# EBook.net
KiCad netlist of a schematic drawn in EAGLE
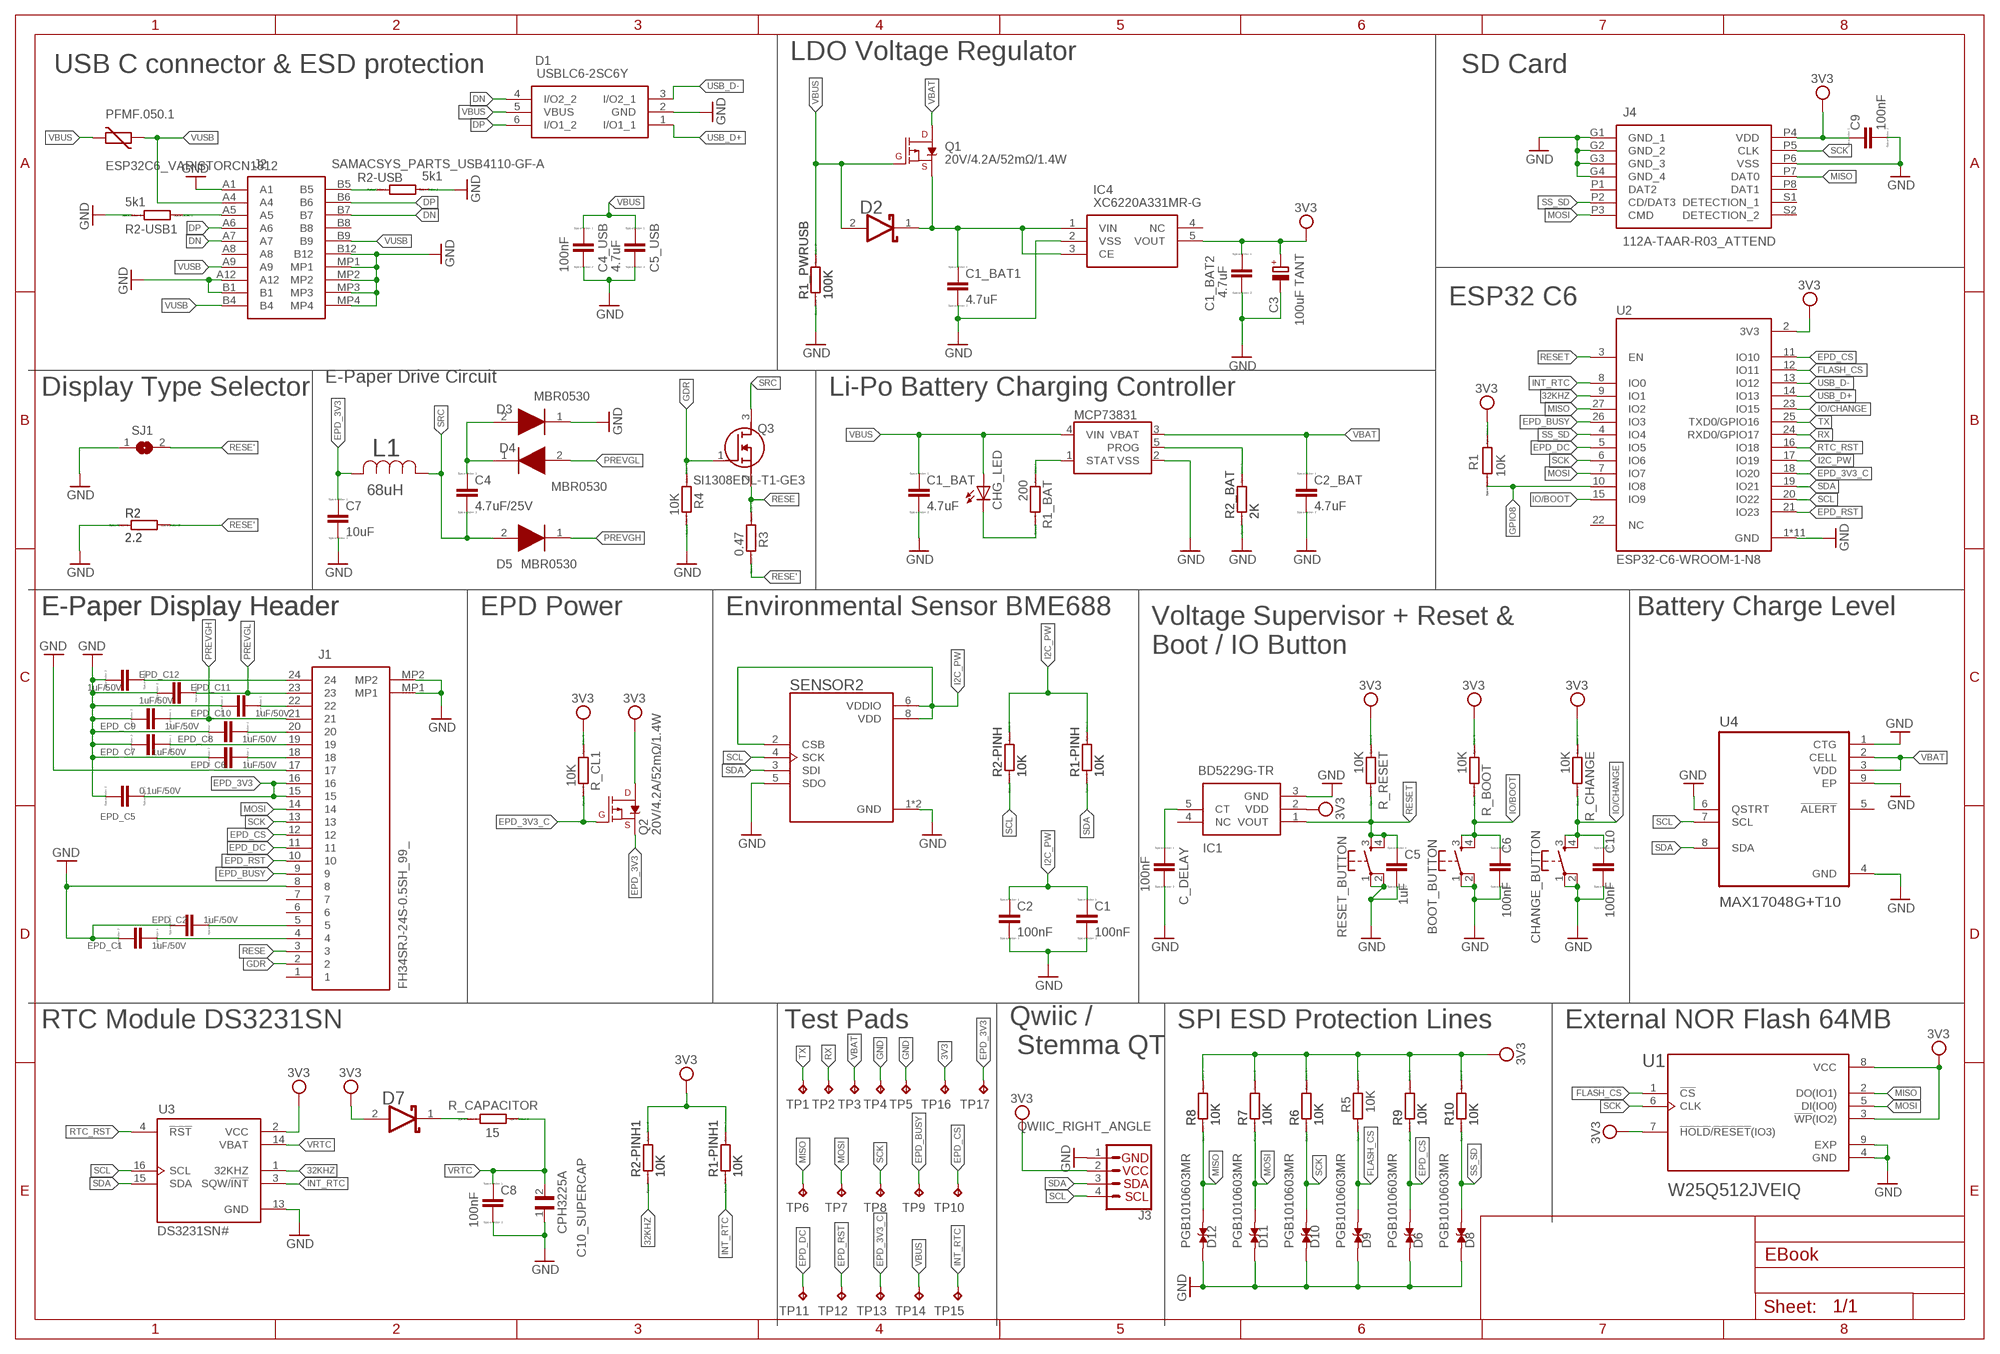
[diagram p0: schematic, sheet 1]

(export (version "E")
  (design (tool "Eeschema 10.0.6"))
  (components
    (comp (ref "BOOT_BUTTON")
      (value "BUTTON_CUSYOMV1")
      (footprint "eagle-import:MYBUTTON")
      (libsource (lib "eagle-import") (part "BUTTON_CUSYOMV1"))
    )
    (comp (ref "C1")
      (value "100nF")
      (footprint "eagle-import:EAGLE-LTSPICE_C0402")
      (libsource (lib "eagle-import") (part "EAGLE-LTSPICE_CC0402"))
    )
    (comp (ref "C1_BAT")
      (value "4.7uF")
      (footprint "eagle-import:EAGLE-LTSPICE_C0402")
      (libsource (lib "eagle-import") (part "EAGLE-LTSPICE_CC0402"))
    )
    (comp (ref "C1_BAT1")
      (value "4.7uF")
      (footprint "eagle-import:EAGLE-LTSPICE_C0402")
      (libsource (lib "eagle-import") (part "EAGLE-LTSPICE_CC0402"))
    )
    (comp (ref "C1_BAT2")
      (value "4.7uF")
      (footprint "eagle-import:EAGLE-LTSPICE_C0402")
      (libsource (lib "eagle-import") (part "EAGLE-LTSPICE_CC0402"))
    )
    (comp (ref "C2")
      (value "100nF")
      (footprint "eagle-import:EAGLE-LTSPICE_C0402")
      (libsource (lib "eagle-import") (part "EAGLE-LTSPICE_CC0402"))
    )
    (comp (ref "C2_BAT")
      (value "4.7uF")
      (footprint "eagle-import:EAGLE-LTSPICE_C0402")
      (libsource (lib "eagle-import") (part "EAGLE-LTSPICE_CC0402"))
    )
    (comp (ref "C3")
      (value "100uF TANT")
      (footprint "eagle-import:RCL_CT3528")
      (libsource (lib "eagle-import") (part "RCL_CPOL-EUCT3528"))
    )
    (comp (ref "C4")
      (value "4.7uF/25V")
      (footprint "eagle-import:EAGLE-LTSPICE_C0402")
      (libsource (lib "eagle-import") (part "EAGLE-LTSPICE_CC0402"))
    )
    (comp (ref "C4_USB")
      (value "100nF")
      (footprint "eagle-import:EAGLE-LTSPICE_C0402")
      (libsource (lib "eagle-import") (part "EAGLE-LTSPICE_CC0402"))
    )
    (comp (ref "C5")
      (value "1uF")
      (footprint "eagle-import:EAGLE-LTSPICE_C0402")
      (libsource (lib "eagle-import") (part "EAGLE-LTSPICE_CC0402"))
    )
    (comp (ref "C5_USB")
      (value "4.7uF")
      (footprint "eagle-import:EAGLE-LTSPICE_C0402")
      (libsource (lib "eagle-import") (part "EAGLE-LTSPICE_CC0402"))
    )
    (comp (ref "C6")
      (value "100nF")
      (footprint "eagle-import:EAGLE-LTSPICE_C0402")
      (libsource (lib "eagle-import") (part "EAGLE-LTSPICE_CC0402"))
    )
    (comp (ref "C7")
      (value "10uF")
      (footprint "eagle-import:EAGLE-LTSPICE_C0402")
      (libsource (lib "eagle-import") (part "EAGLE-LTSPICE_CC0402"))
    )
    (comp (ref "C8")
      (value "100nF")
      (footprint "eagle-import:EAGLE-LTSPICE_C0402")
      (libsource (lib "eagle-import") (part "EAGLE-LTSPICE_CC0402"))
    )
    (comp (ref "C9")
      (value "100nF")
      (footprint "eagle-import:EAGLE-LTSPICE_C0402")
      (libsource (lib "eagle-import") (part "EAGLE-LTSPICE_CC0402"))
    )
    (comp (ref "C10")
      (value "100nF")
      (footprint "eagle-import:EAGLE-LTSPICE_C0402")
      (libsource (lib "eagle-import") (part "EAGLE-LTSPICE_CC0402"))
    )
    (comp (ref "C10_SUPERCAP")
      (value "CPH3225A")
      (footprint "eagle-import:CAPCP3225X100N")
      (fields (field (name "MF") "Seiko Instruments"))
      (libsource (lib "eagle-import") (part "CPH3225A"))
    )
    (comp (ref "CHANGE_BUTTON")
      (value "BUTTON_CUSYOMV1")
      (footprint "eagle-import:MYBUTTON")
      (libsource (lib "eagle-import") (part "BUTTON_CUSYOMV1"))
    )
    (comp (ref "CHG_LED")
      (value "ADAFRUIT_LEDCHIP-LED0603")
      (footprint "eagle-import:ADAFRUIT_CHIP-LED0603")
      (libsource (lib "eagle-import") (part "ADAFRUIT_LEDCHIP-LED0603"))
    )
    (comp (ref "C_DELAY")
      (value "100nF")
      (footprint "eagle-import:EAGLE-LTSPICE_C0402")
      (libsource (lib "eagle-import") (part "EAGLE-LTSPICE_CC0402"))
    )
    (comp (ref "D1")
      (value "USBLC6-2SC6Y")
      (footprint "eagle-import:SOT95P280X145-6N")
      (fields (field (name "MF") "STMicroelectronics"))
      (libsource (lib "eagle-import") (part "USBLC6-2SC6Y"))
    )
    (comp (ref "D2")
      (value "ESP32_WROVER_AVX---SD0805S020S1R0_AVX_SD0805S020S1R0_0_0AVX_SD0805S020S1R0_0_0")
      (footprint "eagle-import:ESP32_WROVER_AVX---SD0805S020S1R0_AVX_SD0805S020S1R0_0")
      (fields
        (field (name "DIGIKEY_PART_NUMBER") "478-7800-1-ND")
        (field (name "MF") "AVX")
        (field (name "MOUSER_PART_NUMBER") "581-SD0805S020S1R0")
      )
      (libsource (lib "eagle-import") (part "ESP32_WROVER_AVX---SD0805S020S1R0_AVX_SD0805S020S1R0_0_0AVX_SD0805S020S1R0_0_0"))
    )
    (comp (ref "D3")
      (value "MBR0530")
      (footprint "eagle-import:SOD3716X135N")
      (fields (field (name "MF") "ON Semiconductor"))
      (libsource (lib "eagle-import") (part "MBR0530"))
    )
    (comp (ref "D4")
      (value "MBR0530")
      (footprint "eagle-import:SOD3716X135N")
      (fields (field (name "MF") "ON Semiconductor"))
      (libsource (lib "eagle-import") (part "MBR0530"))
    )
    (comp (ref "D5")
      (value "MBR0530")
      (footprint "eagle-import:SOD3716X135N")
      (fields (field (name "MF") "ON Semiconductor"))
      (libsource (lib "eagle-import") (part "MBR0530"))
    )
    (comp (ref "D6")
      (value "PGB1010603MR")
      (footprint "eagle-import:DIOC1608X36N")
      (fields (field (name "MF") "Littelfuse Inc."))
      (libsource (lib "eagle-import") (part "PGB1010603MR"))
    )
    (comp (ref "D7")
      (value "ESP32_WROVER_AVX---SD0805S020S1R0_AVX_SD0805S020S1R0_0_0AVX_SD0805S020S1R0_0_0")
      (footprint "eagle-import:ESP32_WROVER_AVX---SD0805S020S1R0_AVX_SD0805S020S1R0_0")
      (fields
        (field (name "DIGIKEY_PART_NUMBER") "478-7800-1-ND")
        (field (name "MF") "AVX")
        (field (name "MOUSER_PART_NUMBER") "581-SD0805S020S1R0")
      )
      (libsource (lib "eagle-import") (part "ESP32_WROVER_AVX---SD0805S020S1R0_AVX_SD0805S020S1R0_0_0AVX_SD0805S020S1R0_0_0"))
    )
    (comp (ref "D8")
      (value "PGB1010603MR")
      (footprint "eagle-import:DIOC1608X36N")
      (fields (field (name "MF") "Littelfuse Inc."))
      (libsource (lib "eagle-import") (part "PGB1010603MR"))
    )
    (comp (ref "D9")
      (value "PGB1010603MR")
      (footprint "eagle-import:DIOC1608X36N")
      (fields (field (name "MF") "Littelfuse Inc."))
      (libsource (lib "eagle-import") (part "PGB1010603MR"))
    )
    (comp (ref "D10")
      (value "PGB1010603MR")
      (footprint "eagle-import:DIOC1608X36N")
      (fields (field (name "MF") "Littelfuse Inc."))
      (libsource (lib "eagle-import") (part "PGB1010603MR"))
    )
    (comp (ref "D11")
      (value "PGB1010603MR")
      (footprint "eagle-import:DIOC1608X36N")
      (fields (field (name "MF") "Littelfuse Inc."))
      (libsource (lib "eagle-import") (part "PGB1010603MR"))
    )
    (comp (ref "D12")
      (value "PGB1010603MR")
      (footprint "eagle-import:DIOC1608X36N")
      (fields (field (name "MF") "Littelfuse Inc."))
      (libsource (lib "eagle-import") (part "PGB1010603MR"))
    )
    (comp (ref "EPD_C1")
      (value "1uF/50V")
      (footprint "eagle-import:EAGLE-LTSPICE_C0402")
      (libsource (lib "eagle-import") (part "EAGLE-LTSPICE_CC0402"))
    )
    (comp (ref "EPD_C2")
      (value "1uF/50V")
      (footprint "eagle-import:EAGLE-LTSPICE_C0402")
      (libsource (lib "eagle-import") (part "EAGLE-LTSPICE_CC0402"))
    )
    (comp (ref "EPD_C5")
      (value "0.1uF/50V")
      (footprint "eagle-import:EAGLE-LTSPICE_C0402")
      (libsource (lib "eagle-import") (part "EAGLE-LTSPICE_CC0402"))
    )
    (comp (ref "EPD_C6")
      (value "1uF/50V")
      (footprint "eagle-import:EAGLE-LTSPICE_C0402")
      (libsource (lib "eagle-import") (part "EAGLE-LTSPICE_CC0402"))
    )
    (comp (ref "EPD_C7")
      (value "1uF/50V")
      (footprint "eagle-import:EAGLE-LTSPICE_C0402")
      (libsource (lib "eagle-import") (part "EAGLE-LTSPICE_CC0402"))
    )
    (comp (ref "EPD_C8")
      (value "1uF/50V")
      (footprint "eagle-import:EAGLE-LTSPICE_C0402")
      (libsource (lib "eagle-import") (part "EAGLE-LTSPICE_CC0402"))
    )
    (comp (ref "EPD_C9")
      (value "1uF/50V")
      (footprint "eagle-import:EAGLE-LTSPICE_C0402")
      (libsource (lib "eagle-import") (part "EAGLE-LTSPICE_CC0402"))
    )
    (comp (ref "EPD_C10")
      (value "1uF/50V")
      (footprint "eagle-import:EAGLE-LTSPICE_C0402")
      (libsource (lib "eagle-import") (part "EAGLE-LTSPICE_CC0402"))
    )
    (comp (ref "EPD_C11")
      (value "1uF/50V")
      (footprint "eagle-import:EAGLE-LTSPICE_C0402")
      (libsource (lib "eagle-import") (part "EAGLE-LTSPICE_CC0402"))
    )
    (comp (ref "EPD_C12")
      (value "1uF/50V")
      (footprint "eagle-import:EAGLE-LTSPICE_C0402")
      (libsource (lib "eagle-import") (part "EAGLE-LTSPICE_CC0402"))
    )
    (comp (ref "IC1")
      (value "BD5229G-TR")
      (footprint "eagle-import:SOT95P280X125-5N")
      (fields (field (name "MOUSER_PART_NUMBER") "755-BD5229G-TR"))
      (libsource (lib "eagle-import") (part "BD5229G-TR"))
    )
    (comp (ref "IC4")
      (value "XC6220A331MR-G")
      (footprint "eagle-import:SOT95P280X120-5N")
      (fields (field (name "MOUSER_PART_NUMBER") "865-XC6220A331MR-G"))
      (libsource (lib "eagle-import") (part "XC6220A331MR-G"))
    )
    (comp (ref "J1")
      (value "FH34SRJ-24S-0.5SH_99_")
      (footprint "eagle-import:FH34SRJ24S05SH99")
      (fields
        (field (name "MANUFACTURER_PART_NUMBER") "FH34SRJ-24S-0.5SH(99)")
        (field (name "MOUSER_PART_NUMBER") "798-FH34SRJ24S05SH99")
      )
      (libsource (lib "eagle-import") (part "FH34SRJ-24S-0.5SH_99_"))
    )
    (comp (ref "J2")
      (value "SAMACSYS_PARTS_USB4110-GF-A")
      (footprint "eagle-import:SAMACSYS_PARTS_USB4110GFA")
      (fields
        (field (name "MANUFACTURER_PART_NUMBER") "USB4110-GF-A")
        (field (name "MOUSER_PART_NUMBER") "640-USB4110-GF-A")
      )
      (libsource (lib "eagle-import") (part "SAMACSYS_PARTS_USB4110-GF-A"))
    )
    (comp (ref "J3")
      (value "QWIIC_RIGHT_ANGLE")
      (footprint "eagle-import:JST04_1MM_RA")
      (libsource (lib "eagle-import") (part "QWIIC_CONNECTORJS-1MM"))
    )
    (comp (ref "J4")
      (value "112A-TAAR-R03_ATTEND")
      (footprint "eagle-import:112ATAARR03ATTEND")
      (fields (field (name "MANUFACTURER_PART_NUMBER") "112A-TAAR-R03 ATTEND"))
      (libsource (lib "eagle-import") (part "112A-TAAR-R03_ATTEND"))
    )
    (comp (ref "L1")
      (value "68uH")
      (footprint "eagle-import:IND_4828-WE-TPC_WRE")
      (fields
        (field (name "MANUFACTURER_PART_NUMBER") "744043680")
        (field (name "COPYRIGHT") "Copyright (C) 2024 Ultra Librarian. All rights reserved.")
      )
      (libsource (lib "eagle-import") (part "744043680IND_4828-WE-TPC_WRE"))
    )
    (comp (ref "MCP73831")
      (value "ESP32_WROVER_SPARKFUN-IC-POWER_MCP73831")
      (footprint "eagle-import:ESP32_WROVER_SPARKFUN-IC-POWER_SOT23-5")
      (libsource (lib "eagle-import") (part "ESP32_WROVER_SPARKFUN-IC-POWER_MCP73831"))
    )
    (comp (ref "PFMF.050.1")
      (value "ESP32C6_VARISTORCN1812")
      (footprint "eagle-import:ESP32C6_VARISTOR_CT_CN1812")
      (libsource (lib "eagle-import") (part "ESP32C6_VARISTORCN1812"))
    )
    (comp (ref "Q1")
      (value "20V/4.2A/52mΩ/1.4W")
      (footprint "eagle-import:ESP32_WROVER_SPARKFUN-DISCRETESEMI_SOT23-3")
      (libsource (lib "eagle-import") (part "ESP32_WROVER_SPARKFUN-DISCRETESEMI_MOSFET_PCH-DMG2305UX-7"))
    )
    (comp (ref "Q2")
      (value "20V/4.2A/52mΩ/1.4W")
      (footprint "eagle-import:ESP32_WROVER_SPARKFUN-DISCRETESEMI_SOT23-3")
      (libsource (lib "eagle-import") (part "ESP32_WROVER_SPARKFUN-DISCRETESEMI_MOSFET_PCH-DMG2305UX-7"))
    )
    (comp (ref "Q3")
      (value "SI1308EDL-T1-GE3")
      (footprint "eagle-import:SOT65P210X110-3N")
      (fields (field (name "MF") "Vishay Siliconix"))
      (libsource (lib "eagle-import") (part "SI1308EDL-T1-GE3"))
    )
    (comp (ref "R1")
      (value "10K")
      (footprint "eagle-import:ESP32_WROVER_EAGLE-LTSPICE_R0402")
      (libsource (lib "eagle-import") (part "ESP32_WROVER_EAGLE-LTSPICE_RR0402"))
    )
    (comp (ref "R1-PINH")
      (value "10K")
      (footprint "eagle-import:ESP32_WROVER_EAGLE-LTSPICE_R0402")
      (libsource (lib "eagle-import") (part "ESP32_WROVER_EAGLE-LTSPICE_RR0402"))
    )
    (comp (ref "R1-PINH1")
      (value "10K")
      (footprint "eagle-import:ESP32_WROVER_EAGLE-LTSPICE_R0402")
      (libsource (lib "eagle-import") (part "ESP32_WROVER_EAGLE-LTSPICE_RR0402"))
    )
    (comp (ref "R1_BAT")
      (value "200")
      (footprint "eagle-import:ESP32_WROVER_EAGLE-LTSPICE_R0402")
      (libsource (lib "eagle-import") (part "ESP32_WROVER_EAGLE-LTSPICE_RR0402"))
    )
    (comp (ref "R1_PWRUSB")
      (value "100K")
      (footprint "eagle-import:ESP32_WROVER_EAGLE-LTSPICE_R0402")
      (libsource (lib "eagle-import") (part "ESP32_WROVER_EAGLE-LTSPICE_RR0402"))
    )
    (comp (ref "R2")
      (value "2.2")
      (footprint "eagle-import:ESP32_WROVER_EAGLE-LTSPICE_R0402")
      (libsource (lib "eagle-import") (part "ESP32_WROVER_EAGLE-LTSPICE_RR0402"))
    )
    (comp (ref "R2-PINH")
      (value "10K")
      (footprint "eagle-import:ESP32_WROVER_EAGLE-LTSPICE_R0402")
      (libsource (lib "eagle-import") (part "ESP32_WROVER_EAGLE-LTSPICE_RR0402"))
    )
    (comp (ref "R2-PINH1")
      (value "10K")
      (footprint "eagle-import:ESP32_WROVER_EAGLE-LTSPICE_R0402")
      (libsource (lib "eagle-import") (part "ESP32_WROVER_EAGLE-LTSPICE_RR0402"))
    )
    (comp (ref "R2-USB")
      (value "5k1")
      (footprint "eagle-import:ESP32_WROVER_EAGLE-LTSPICE_R0402")
      (libsource (lib "eagle-import") (part "ESP32_WROVER_EAGLE-LTSPICE_RR0402"))
    )
    (comp (ref "R2-USB1")
      (value "5k1")
      (footprint "eagle-import:ESP32_WROVER_EAGLE-LTSPICE_R0402")
      (libsource (lib "eagle-import") (part "ESP32_WROVER_EAGLE-LTSPICE_RR0402"))
    )
    (comp (ref "R2_BAT")
      (value "2K")
      (footprint "eagle-import:ESP32_WROVER_EAGLE-LTSPICE_R0402")
      (libsource (lib "eagle-import") (part "ESP32_WROVER_EAGLE-LTSPICE_RR0402"))
    )
    (comp (ref "R3")
      (value "0.47")
      (footprint "eagle-import:ESP32_WROVER_EAGLE-LTSPICE_R0402")
      (libsource (lib "eagle-import") (part "ESP32_WROVER_EAGLE-LTSPICE_RR0402"))
    )
    (comp (ref "R4")
      (value "10K")
      (footprint "eagle-import:ESP32_WROVER_EAGLE-LTSPICE_R0402")
      (libsource (lib "eagle-import") (part "ESP32_WROVER_EAGLE-LTSPICE_RR0402"))
    )
    (comp (ref "R5")
      (value "10K")
      (footprint "eagle-import:ESP32_WROVER_EAGLE-LTSPICE_R0402")
      (libsource (lib "eagle-import") (part "ESP32_WROVER_EAGLE-LTSPICE_RR0402"))
    )
    (comp (ref "R6")
      (value "10K")
      (footprint "eagle-import:ESP32_WROVER_EAGLE-LTSPICE_R0402")
      (libsource (lib "eagle-import") (part "ESP32_WROVER_EAGLE-LTSPICE_RR0402"))
    )
    (comp (ref "R7")
      (value "10K")
      (footprint "eagle-import:ESP32_WROVER_EAGLE-LTSPICE_R0402")
      (libsource (lib "eagle-import") (part "ESP32_WROVER_EAGLE-LTSPICE_RR0402"))
    )
    (comp (ref "R8")
      (value "10K")
      (footprint "eagle-import:ESP32_WROVER_EAGLE-LTSPICE_R0402")
      (libsource (lib "eagle-import") (part "ESP32_WROVER_EAGLE-LTSPICE_RR0402"))
    )
    (comp (ref "R9")
      (value "10K")
      (footprint "eagle-import:ESP32_WROVER_EAGLE-LTSPICE_R0402")
      (libsource (lib "eagle-import") (part "ESP32_WROVER_EAGLE-LTSPICE_RR0402"))
    )
    (comp (ref "R10")
      (value "10K")
      (footprint "eagle-import:ESP32_WROVER_EAGLE-LTSPICE_R0402")
      (libsource (lib "eagle-import") (part "ESP32_WROVER_EAGLE-LTSPICE_RR0402"))
    )
    (comp (ref "RESET_BUTTON")
      (value "BUTTON_CUSYOMV1")
      (footprint "eagle-import:MYBUTTON")
      (libsource (lib "eagle-import") (part "BUTTON_CUSYOMV1"))
    )
    (comp (ref "R_BOOT")
      (value "10K")
      (footprint "eagle-import:ESP32_WROVER_EAGLE-LTSPICE_R0402")
      (libsource (lib "eagle-import") (part "ESP32_WROVER_EAGLE-LTSPICE_RR0402"))
    )
    (comp (ref "R_CAPACITOR")
      (value "15")
      (footprint "eagle-import:ESP32_WROVER_EAGLE-LTSPICE_R0402")
      (libsource (lib "eagle-import") (part "ESP32_WROVER_EAGLE-LTSPICE_RR0402"))
    )
    (comp (ref "R_CHANGE")
      (value "10K")
      (footprint "eagle-import:ESP32_WROVER_EAGLE-LTSPICE_R0402")
      (libsource (lib "eagle-import") (part "ESP32_WROVER_EAGLE-LTSPICE_RR0402"))
    )
    (comp (ref "R_CL1")
      (value "10K")
      (footprint "eagle-import:ESP32_WROVER_EAGLE-LTSPICE_R0402")
      (libsource (lib "eagle-import") (part "ESP32_WROVER_EAGLE-LTSPICE_RR0402"))
    )
    (comp (ref "R_RESET")
      (value "10K")
      (footprint "eagle-import:ESP32_WROVER_EAGLE-LTSPICE_R0402")
      (libsource (lib "eagle-import") (part "ESP32_WROVER_EAGLE-LTSPICE_RR0402"))
    )
    (comp (ref "SENSOR2")
      (value "ESP32_WROVER_BME680_BME680")
      (footprint "eagle-import:ESP32_WROVER_BME680_PSON80P300X300X100-8N")
      (fields (field (name "MF") "Bosch Sensortec") (field (name "MP") "BME680"))
      (libsource (lib "eagle-import") (part "ESP32_WROVER_BME680_BME680"))
    )
    (comp (ref "SJ1") (value "SJ") (footprint "eagle-import:SJ") (libsource (lib "eagle-import") (part "SJ")))
    (comp (ref "TP1")
      (value "TPTP20R")
      (footprint "eagle-import:TP20R")
      (libsource (lib "eagle-import") (part "TPTP20R"))
    )
    (comp (ref "TP2")
      (value "TPTP20R")
      (footprint "eagle-import:TP20R")
      (libsource (lib "eagle-import") (part "TPTP20R"))
    )
    (comp (ref "TP3")
      (value "TPTP20R")
      (footprint "eagle-import:TP20R")
      (libsource (lib "eagle-import") (part "TPTP20R"))
    )
    (comp (ref "TP4")
      (value "TPTP20R")
      (footprint "eagle-import:TP20R")
      (libsource (lib "eagle-import") (part "TPTP20R"))
    )
    (comp (ref "TP5")
      (value "TPTP20R")
      (footprint "eagle-import:TP20R")
      (libsource (lib "eagle-import") (part "TPTP20R"))
    )
    (comp (ref "TP6")
      (value "TPTP20R")
      (footprint "eagle-import:TP20R")
      (libsource (lib "eagle-import") (part "TPTP20R"))
    )
    (comp (ref "TP7")
      (value "TPTP20R")
      (footprint "eagle-import:TP20R")
      (libsource (lib "eagle-import") (part "TPTP20R"))
    )
    (comp (ref "TP8")
      (value "TPTP20R")
      (footprint "eagle-import:TP20R")
      (libsource (lib "eagle-import") (part "TPTP20R"))
    )
    (comp (ref "TP9")
      (value "TPTP20R")
      (footprint "eagle-import:TP20R")
      (libsource (lib "eagle-import") (part "TPTP20R"))
    )
    (comp (ref "TP10")
      (value "TPTP20R")
      (footprint "eagle-import:TP20R")
      (libsource (lib "eagle-import") (part "TPTP20R"))
    )
    (comp (ref "TP11")
      (value "TPTP20R")
      (footprint "eagle-import:TP20R")
      (libsource (lib "eagle-import") (part "TPTP20R"))
    )
    (comp (ref "TP12")
      (value "TPTP20R")
      (footprint "eagle-import:TP20R")
      (libsource (lib "eagle-import") (part "TPTP20R"))
    )
    (comp (ref "TP13")
      (value "TPTP20R")
      (footprint "eagle-import:TP20R")
      (libsource (lib "eagle-import") (part "TPTP20R"))
    )
    (comp (ref "TP14")
      (value "TPTP20R")
      (footprint "eagle-import:TP20R")
      (libsource (lib "eagle-import") (part "TPTP20R"))
    )
    (comp (ref "TP15")
      (value "TPTP20R")
      (footprint "eagle-import:TP20R")
      (libsource (lib "eagle-import") (part "TPTP20R"))
    )
    (comp (ref "TP16")
      (value "TPTP20R")
      (footprint "eagle-import:TP20R")
      (libsource (lib "eagle-import") (part "TPTP20R"))
    )
    (comp (ref "TP17")
      (value "TPTP20R")
      (footprint "eagle-import:TP20R")
      (libsource (lib "eagle-import") (part "TPTP20R"))
    )
    (comp (ref "U1")
      (value "W25Q512JVEIQ")
      (footprint "eagle-import:SON127P600X800X80-9N")
      (fields (field (name "MF") "Winbond Electronics"))
      (libsource (lib "eagle-import") (part "W25Q512JVEIQ"))
    )
    (comp (ref "U2")
      (value "ESP32-C6-WROOM-1-N8")
      (footprint "eagle-import:XCVR_ESP32-C6-WROOM-1-N8")
      (fields (field (name "MF") "Espressif Systems"))
      (libsource (lib "eagle-import") (part "ESP32-C6-WROOM-1-N8"))
    )
    (comp (ref "U3")
      (value "DS3231SN#")
      (footprint "eagle-import:SOIC127P1032X265-16N")
      (fields (field (name "MF") "Analog Devices"))
      (libsource (lib "eagle-import") (part "DS3231SN#"))
    )
    (comp (ref "U4")
      (value "MAX17048G+T10")
      (footprint "eagle-import:SON50P200X200X80-9N")
      (fields (field (name "MF") "Analog Devices"))
      (libsource (lib "eagle-import") (part "MAX17048G+T10"))
    )
  )
  (nets
    (net (code "1") (name "3V3") (class "Default")
      (node (ref "C1_BAT2") (pin "1") (pinfunction "1_1") (pintype "passive"))
      (node (ref "C3") (pin "+") (pinfunction "+_+") (pintype "passive"))
      (node (ref "C9") (pin "1") (pinfunction "1_1") (pintype "passive"))
      (node (ref "D7") (pin "2") (pinfunction "ANODE_2") (pintype "bidirectional"))
      (node (ref "IC1") (pin "2") (pinfunction "VDD_2") (pintype "bidirectional"))
      (node (ref "IC4") (pin "5") (pinfunction "VOUT_5") (pintype "bidirectional"))
      (node (ref "J3") (pin "2") (pinfunction "2_2") (pintype "power_in"))
      (node (ref "J4") (pin "P4") (pinfunction "VDD_P4") (pintype "bidirectional"))
      (node (ref "Q2") (pin "3") (pinfunction "D_3") (pintype "bidirectional"))
      (node (ref "R1") (pin "1") (pinfunction "1_1") (pintype "passive"))
      (node (ref "R1-PINH1") (pin "2") (pinfunction "2_2") (pintype "passive"))
      (node (ref "R10") (pin "2") (pinfunction "2_2") (pintype "passive"))
      (node (ref "R2-PINH1") (pin "2") (pinfunction "2_2") (pintype "passive"))
      (node (ref "R5") (pin "2") (pinfunction "2_2") (pintype "passive"))
      (node (ref "R6") (pin "2") (pinfunction "2_2") (pintype "passive"))
      (node (ref "R7") (pin "2") (pinfunction "2_2") (pintype "passive"))
      (node (ref "R8") (pin "2") (pinfunction "2_2") (pintype "passive"))
      (node (ref "R9") (pin "2") (pinfunction "2_2") (pintype "passive"))
      (node (ref "R_BOOT") (pin "1") (pinfunction "1_1") (pintype "passive"))
      (node (ref "R_CHANGE") (pin "1") (pinfunction "1_1") (pintype "passive"))
      (node (ref "R_CL1") (pin "1") (pinfunction "1_1") (pintype "passive"))
      (node (ref "R_RESET") (pin "1") (pinfunction "1_1") (pintype "passive"))
      (node (ref "TP16") (pin "TP") (pinfunction "TP_TP") (pintype "input"))
      (node (ref "U1") (pin "3") (pinfunction "~{WP}(IO2)_3") (pintype "bidirectional"))
      (node (ref "U1") (pin "7") (pinfunction "~{HOLD}/~{RESET}(IO3)_7") (pintype "bidirectional"))
      (node (ref "U1") (pin "8") (pinfunction "VCC_8") (pintype "power_in"))
      (node (ref "U2") (pin "2") (pinfunction "3V3_2") (pintype "power_in"))
      (node (ref "U3") (pin "2") (pinfunction "VCC_2") (pintype "power_in"))
    )
    (net (code "2") (name "32KHZ") (class "Default")
      (node (ref "R2-PINH1") (pin "1") (pinfunction "1_1") (pintype "passive"))
      (node (ref "U2") (pin "9") (pinfunction "IO1_9") (pintype "bidirectional"))
      (node (ref "U3") (pin "1") (pinfunction "32KHZ_1") (pintype "output"))
    )
    (net (code "3") (name "DN") (class "Default")
      (node (ref "D1") (pin "4") (pinfunction "I/O2_2_4") (pintype "bidirectional"))
      (node (ref "J2") (pin "A7") (pinfunction "A7_A7") (pintype "bidirectional"))
      (node (ref "J2") (pin "B7") (pinfunction "B7_B7") (pintype "bidirectional"))
    )
    (net (code "4") (name "DP") (class "Default")
      (node (ref "D1") (pin "6") (pinfunction "I/O1_2_6") (pintype "bidirectional"))
      (node (ref "J2") (pin "A6") (pinfunction "A6_A6") (pintype "bidirectional"))
      (node (ref "J2") (pin "B6") (pinfunction "B6_B6") (pintype "bidirectional"))
    )
    (net (code "5") (name "EPD_3V3") (class "Default")
      (node (ref "C7") (pin "1") (pinfunction "1_1") (pintype "passive"))
      (node (ref "EPD_C5") (pin "1") (pinfunction "1_1") (pintype "passive"))
      (node (ref "J1") (pin "15") (pinfunction "15_15") (pintype "bidirectional"))
      (node (ref "J1") (pin "16") (pinfunction "16_16") (pintype "bidirectional"))
      (node (ref "L1") (pin "2") (pinfunction "2_2") (pintype "passive"))
      (node (ref "Q2") (pin "2") (pinfunction "S_2") (pintype "bidirectional"))
      (node (ref "TP17") (pin "TP") (pinfunction "TP_TP") (pintype "input"))
    )
    (net (code "6") (name "EPD_3V3_C") (class "Default")
      (node (ref "Q2") (pin "1") (pinfunction "G_1") (pintype "bidirectional"))
      (node (ref "R_CL1") (pin "2") (pinfunction "2_2") (pintype "passive"))
      (node (ref "TP13") (pin "TP") (pinfunction "TP_TP") (pintype "input"))
      (node (ref "U2") (pin "18") (pinfunction "IO20_18") (pintype "bidirectional"))
    )
    (net (code "7") (name "EPD_BUSY") (class "Default")
      (node (ref "J1") (pin "9") (pinfunction "9_9") (pintype "bidirectional"))
      (node (ref "TP9") (pin "TP") (pinfunction "TP_TP") (pintype "input"))
      (node (ref "U2") (pin "26") (pinfunction "IO3_26") (pintype "bidirectional"))
    )
    (net (code "8") (name "EPD_CS") (class "Default")
      (node (ref "D6") (pin "2") (pinfunction "2_2") (pintype "passive"))
      (node (ref "J1") (pin "12") (pinfunction "12_12") (pintype "bidirectional"))
      (node (ref "R9") (pin "1") (pinfunction "1_1") (pintype "passive"))
      (node (ref "TP10") (pin "TP") (pinfunction "TP_TP") (pintype "input"))
      (node (ref "U2") (pin "11") (pinfunction "IO10_11") (pintype "bidirectional"))
    )
    (net (code "9") (name "EPD_DC") (class "Default")
      (node (ref "J1") (pin "11") (pinfunction "11_11") (pintype "bidirectional"))
      (node (ref "TP11") (pin "TP") (pinfunction "TP_TP") (pintype "input"))
      (node (ref "U2") (pin "5") (pinfunction "IO5_5") (pintype "bidirectional"))
    )
    (net (code "10") (name "EPD_RST") (class "Default")
      (node (ref "J1") (pin "10") (pinfunction "10_10") (pintype "bidirectional"))
      (node (ref "TP12") (pin "TP") (pinfunction "TP_TP") (pintype "input"))
      (node (ref "U2") (pin "21") (pinfunction "IO23_21") (pintype "bidirectional"))
    )
    (net (code "11") (name "FLASH_CS") (class "Default")
      (node (ref "D9") (pin "2") (pinfunction "2_2") (pintype "passive"))
      (node (ref "R5") (pin "1") (pinfunction "1_1") (pintype "passive"))
      (node (ref "U1") (pin "1") (pinfunction "~{CS}_1") (pintype "input"))
      (node (ref "U2") (pin "12") (pinfunction "IO11_12") (pintype "bidirectional"))
    )
    (net (code "12") (name "GDR") (class "Default")
      (node (ref "J1") (pin "2") (pinfunction "2_2") (pintype "bidirectional"))
      (node (ref "Q3") (pin "1") (pinfunction "G_1") (pintype "bidirectional"))
      (node (ref "R4") (pin "1") (pinfunction "1_1") (pintype "passive"))
    )
    (net (code "13") (name "GND") (class "Default")
      (node (ref "BOOT_BUTTON") (pin "1") (pinfunction "1_1") (pintype "passive"))
      (node (ref "BOOT_BUTTON") (pin "2") (pinfunction "2_2") (pintype "passive"))
      (node (ref "C1") (pin "2") (pinfunction "2_2") (pintype "passive"))
      (node (ref "C10") (pin "2") (pinfunction "2_2") (pintype "passive"))
      (node (ref "C10_SUPERCAP") (pin "1") (pinfunction "1_1") (pintype "passive"))
      (node (ref "C1_BAT") (pin "2") (pinfunction "2_2") (pintype "passive"))
      (node (ref "C1_BAT1") (pin "2") (pinfunction "2_2") (pintype "passive"))
      (node (ref "C1_BAT2") (pin "2") (pinfunction "2_2") (pintype "passive"))
      (node (ref "C2") (pin "2") (pinfunction "2_2") (pintype "passive"))
      (node (ref "C2_BAT") (pin "2") (pinfunction "2_2") (pintype "passive"))
      (node (ref "C3") (pin "-") (pinfunction "-_-") (pintype "passive"))
      (node (ref "C4_USB") (pin "2") (pinfunction "2_2") (pintype "passive"))
      (node (ref "C5") (pin "2") (pinfunction "2_2") (pintype "passive"))
      (node (ref "C5_USB") (pin "2") (pinfunction "2_2") (pintype "passive"))
      (node (ref "C6") (pin "2") (pinfunction "2_2") (pintype "passive"))
      (node (ref "C7") (pin "2") (pinfunction "2_2") (pintype "passive"))
      (node (ref "C8") (pin "2") (pinfunction "2_2") (pintype "passive"))
      (node (ref "C9") (pin "2") (pinfunction "2_2") (pintype "passive"))
      (node (ref "CHANGE_BUTTON") (pin "1") (pinfunction "1_1") (pintype "passive"))
      (node (ref "CHANGE_BUTTON") (pin "2") (pinfunction "2_2") (pintype "passive"))
      (node (ref "C_DELAY") (pin "2") (pinfunction "2_2") (pintype "passive"))
      (node (ref "D1") (pin "2") (pinfunction "GND_2") (pintype "bidirectional"))
      (node (ref "D10") (pin "1") (pinfunction "1_1") (pintype "passive"))
      (node (ref "D11") (pin "1") (pinfunction "1_1") (pintype "passive"))
      (node (ref "D12") (pin "1") (pinfunction "1_1") (pintype "passive"))
      (node (ref "D3") (pin "1") (pinfunction "K_1") (pintype "bidirectional"))
      (node (ref "D6") (pin "1") (pinfunction "1_1") (pintype "passive"))
      (node (ref "D8") (pin "1") (pinfunction "1_1") (pintype "passive"))
      (node (ref "D9") (pin "1") (pinfunction "1_1") (pintype "passive"))
      (node (ref "EPD_C1") (pin "2") (pinfunction "2_2") (pintype "passive"))
      (node (ref "EPD_C10") (pin "2") (pinfunction "2_2") (pintype "passive"))
      (node (ref "EPD_C11") (pin "2") (pinfunction "2_2") (pintype "passive"))
      (node (ref "EPD_C12") (pin "2") (pinfunction "2_2") (pintype "passive"))
      (node (ref "EPD_C2") (pin "2") (pinfunction "2_2") (pintype "passive"))
      (node (ref "EPD_C5") (pin "2") (pinfunction "2_2") (pintype "passive"))
      (node (ref "EPD_C6") (pin "2") (pinfunction "2_2") (pintype "passive"))
      (node (ref "EPD_C7") (pin "2") (pinfunction "2_2") (pintype "passive"))
      (node (ref "EPD_C8") (pin "2") (pinfunction "2_2") (pintype "passive"))
      (node (ref "EPD_C9") (pin "2") (pinfunction "2_2") (pintype "passive"))
      (node (ref "IC1") (pin "3") (pinfunction "GND_3") (pintype "bidirectional"))
      (node (ref "IC4") (pin "2") (pinfunction "VSS_2") (pintype "bidirectional"))
      (node (ref "J1") (pin "17") (pinfunction "17_17") (pintype "bidirectional"))
      (node (ref "J1") (pin "8") (pinfunction "8_8") (pintype "bidirectional"))
      (node (ref "J1") (pin "MP1") (pinfunction "MP1_MP1") (pintype "bidirectional"))
      (node (ref "J1") (pin "MP2") (pinfunction "MP2_MP2") (pintype "bidirectional"))
      (node (ref "J2") (pin "A1") (pinfunction "A1_A1") (pintype "bidirectional"))
      (node (ref "J2") (pin "A12") (pinfunction "A12_A12") (pintype "bidirectional"))
      (node (ref "J2") (pin "B1") (pinfunction "B1_B1") (pintype "bidirectional"))
      (node (ref "J2") (pin "B12") (pinfunction "B12_B12") (pintype "bidirectional"))
      (node (ref "J2") (pin "MP1") (pinfunction "MP1_MP1") (pintype "bidirectional"))
      (node (ref "J2") (pin "MP2") (pinfunction "MP2_MP2") (pintype "bidirectional"))
      (node (ref "J2") (pin "MP3") (pinfunction "MP3_MP3") (pintype "bidirectional"))
      (node (ref "J2") (pin "MP4") (pinfunction "MP4_MP4") (pintype "bidirectional"))
      (node (ref "J3") (pin "1") (pinfunction "1_1") (pintype "power_in"))
      (node (ref "J4") (pin "G1") (pinfunction "GND_1_G1") (pintype "bidirectional"))
      (node (ref "J4") (pin "G2") (pinfunction "GND_2_G2") (pintype "bidirectional"))
      (node (ref "J4") (pin "G3") (pinfunction "GND_3_G3") (pintype "bidirectional"))
      (node (ref "J4") (pin "G4") (pinfunction "GND_4_G4") (pintype "bidirectional"))
      (node (ref "J4") (pin "P6") (pinfunction "VSS_P6") (pintype "bidirectional"))
      (node (ref "MCP73831") (pin "2") (pinfunction "VSS_2") (pintype "power_in"))
      (node (ref "R1_PWRUSB") (pin "1") (pinfunction "1_1") (pintype "passive"))
      (node (ref "R2") (pin "1") (pinfunction "1_1") (pintype "passive"))
      (node (ref "R2-USB") (pin "2") (pinfunction "2_2") (pintype "passive"))
      (node (ref "R2-USB1") (pin "1") (pinfunction "1_1") (pintype "passive"))
      (node (ref "R2_BAT") (pin "1") (pinfunction "1_1") (pintype "passive"))
      (node (ref "R4") (pin "2") (pinfunction "2_2") (pintype "passive"))
      (node (ref "RESET_BUTTON") (pin "1") (pinfunction "1_1") (pintype "passive"))
      (node (ref "RESET_BUTTON") (pin "2") (pinfunction "2_2") (pintype "passive"))
      (node (ref "SENSOR2") (pin "1") (pinfunction "GND_1") (pintype "power_in"))
      (node (ref "SENSOR2") (pin "5") (pinfunction "SDO_5") (pintype "bidirectional"))
      (node (ref "SENSOR2") (pin "7") (pinfunction "GND_7") (pintype "power_in"))
      (node (ref "SJ1") (pin "1") (pinfunction "1_1") (pintype "passive"))
      (node (ref "TP4") (pin "TP") (pinfunction "TP_TP") (pintype "input"))
      (node (ref "TP5") (pin "TP") (pinfunction "TP_TP") (pintype "input"))
      (node (ref "U1") (pin "4") (pinfunction "GND_4") (pintype "power_in"))
      (node (ref "U1") (pin "9") (pinfunction "EXP_9") (pintype "passive"))
      (node (ref "U2") (pin "1") (pinfunction "GND_1") (pintype "power_in"))
      (node (ref "U2") (pin "28") (pinfunction "GND_28") (pintype "power_in"))
      (node (ref "U2") (pin "29_1") (pinfunction "GND_29_1") (pintype "power_in"))
      (node (ref "U2") (pin "29_2") (pinfunction "GND_29_2") (pintype "power_in"))
      (node (ref "U2") (pin "29_3") (pinfunction "GND_29_3") (pintype "power_in"))
      (node (ref "U2") (pin "29_4") (pinfunction "GND_29_4") (pintype "power_in"))
      (node (ref "U2") (pin "29_5") (pinfunction "GND_29_5") (pintype "power_in"))
      (node (ref "U2") (pin "29_6") (pinfunction "GND_29_6") (pintype "power_in"))
      (node (ref "U2") (pin "29_7") (pinfunction "GND_29_7") (pintype "power_in"))
      (node (ref "U2") (pin "29_8") (pinfunction "GND_29_8") (pintype "power_in"))
      (node (ref "U2") (pin "29_9") (pinfunction "GND_29_9") (pintype "power_in"))
      (node (ref "U3") (pin "13") (pinfunction "GND_13") (pintype "power_in"))
      (node (ref "U4") (pin "1") (pinfunction "CTG_1") (pintype "power_in"))
      (node (ref "U4") (pin "4") (pinfunction "GND_4") (pintype "power_in"))
      (node (ref "U4") (pin "6") (pinfunction "QSTRT_6") (pintype "input"))
      (node (ref "U4") (pin "9") (pinfunction "EP_9") (pintype "power_in"))
    )
    (net (code "14") (name "GPIO8") (class "Default")
      (node (ref "R1") (pin "2") (pinfunction "2_2") (pintype "passive"))
      (node (ref "U2") (pin "10") (pinfunction "IO8_10") (pintype "bidirectional"))
    )
    (net (code "15") (name "I2C_PW") (class "Default")
      (node (ref "C1") (pin "1") (pinfunction "1_1") (pintype "passive"))
      (node (ref "C2") (pin "1") (pinfunction "1_1") (pintype "passive"))
      (node (ref "R1-PINH") (pin "2") (pinfunction "2_2") (pintype "passive"))
      (node (ref "R2-PINH") (pin "2") (pinfunction "2_2") (pintype "passive"))
      (node (ref "SENSOR2") (pin "2") (pinfunction "CSB_2") (pintype "input"))
      (node (ref "SENSOR2") (pin "6") (pinfunction "VDDIO_6") (pintype "power_in"))
      (node (ref "SENSOR2") (pin "8") (pinfunction "VDD_8") (pintype "power_in"))
      (node (ref "U2") (pin "17") (pinfunction "IO19_17") (pintype "bidirectional"))
    )
    (net (code "16") (name "INT_RTC") (class "Default")
      (node (ref "R1-PINH1") (pin "1") (pinfunction "1_1") (pintype "passive"))
      (node (ref "TP15") (pin "TP") (pinfunction "TP_TP") (pintype "input"))
      (node (ref "U2") (pin "8") (pinfunction "IO0_8") (pintype "bidirectional"))
      (node (ref "U3") (pin "3") (pinfunction "SQW/~{INT}_3") (pintype "output"))
    )
    (net (code "17") (name "IO{slash}BOOT") (class "Default")
      (node (ref "BOOT_BUTTON") (pin "3") (pinfunction "3_3") (pintype "passive"))
      (node (ref "BOOT_BUTTON") (pin "4") (pinfunction "4_4") (pintype "passive"))
      (node (ref "C6") (pin "1") (pinfunction "1_1") (pintype "passive"))
      (node (ref "R_BOOT") (pin "2") (pinfunction "2_2") (pintype "passive"))
      (node (ref "U2") (pin "15") (pinfunction "IO9_15") (pintype "bidirectional"))
    )
    (net (code "18") (name "IO{slash}CHANGE") (class "Default")
      (node (ref "C10") (pin "1") (pinfunction "1_1") (pintype "passive"))
      (node (ref "CHANGE_BUTTON") (pin "3") (pinfunction "3_3") (pintype "passive"))
      (node (ref "CHANGE_BUTTON") (pin "4") (pinfunction "4_4") (pintype "passive"))
      (node (ref "R_CHANGE") (pin "2") (pinfunction "2_2") (pintype "passive"))
      (node (ref "U2") (pin "23") (pinfunction "IO15_23") (pintype "bidirectional"))
    )
    (net (code "19") (name "MISO") (class "Default")
      (node (ref "D12") (pin "2") (pinfunction "2_2") (pintype "passive"))
      (node (ref "J4") (pin "P7") (pinfunction "DAT0_P7") (pintype "bidirectional"))
      (node (ref "R8") (pin "1") (pinfunction "1_1") (pintype "passive"))
      (node (ref "TP6") (pin "TP") (pinfunction "TP_TP") (pintype "input"))
      (node (ref "U1") (pin "2") (pinfunction "DO(IO1)_2") (pintype "bidirectional"))
      (node (ref "U2") (pin "27") (pinfunction "IO2_27") (pintype "bidirectional"))
    )
    (net (code "20") (name "MOSI") (class "Default")
      (node (ref "D11") (pin "2") (pinfunction "2_2") (pintype "passive"))
      (node (ref "J1") (pin "14") (pinfunction "14_14") (pintype "bidirectional"))
      (node (ref "J4") (pin "P3") (pinfunction "CMD_P3") (pintype "bidirectional"))
      (node (ref "R7") (pin "1") (pinfunction "1_1") (pintype "passive"))
      (node (ref "TP7") (pin "TP") (pinfunction "TP_TP") (pintype "input"))
      (node (ref "U1") (pin "5") (pinfunction "DI(IO0)_5") (pintype "bidirectional"))
      (node (ref "U2") (pin "7") (pinfunction "IO7_7") (pintype "bidirectional"))
    )
    (net (code "21") (name "Net-(CHG_LED-PadC)") (class "Default")
      (node (ref "CHG_LED") (pin "C") (pinfunction "C_C") (pintype "passive"))
      (node (ref "R1_BAT") (pin "2") (pinfunction "2_2") (pintype "passive"))
    )
    (net (code "22") (name "Net-(D2-CATHODE)") (class "Default")
      (node (ref "C1_BAT1") (pin "1") (pinfunction "1_1") (pintype "passive"))
      (node (ref "D2") (pin "1") (pinfunction "CATHODE_1") (pintype "bidirectional"))
      (node (ref "IC4") (pin "1") (pinfunction "VIN_1") (pintype "bidirectional"))
      (node (ref "IC4") (pin "3") (pinfunction "CE_3") (pintype "bidirectional"))
      (node (ref "Q1") (pin "2") (pinfunction "S_2") (pintype "bidirectional"))
    )
    (net (code "23") (name "Net-(D3-A)") (class "Default")
      (node (ref "C4") (pin "1") (pinfunction "1_1") (pintype "passive"))
      (node (ref "D3") (pin "2") (pinfunction "A_2") (pintype "bidirectional"))
      (node (ref "D4") (pin "1") (pinfunction "K_1") (pintype "bidirectional"))
    )
    (net (code "24") (name "Net-(D7-CATHODE)") (class "Default")
      (node (ref "D7") (pin "1") (pinfunction "CATHODE_1") (pintype "bidirectional"))
      (node (ref "R_CAPACITOR") (pin "2") (pinfunction "2_2") (pintype "passive"))
    )
    (net (code "25") (name "Net-(EPD_C1-Pad1)") (class "Default")
      (node (ref "EPD_C1") (pin "1") (pinfunction "1_1") (pintype "passive"))
      (node (ref "J1") (pin "4") (pinfunction "4_4") (pintype "bidirectional"))
    )
    (net (code "26") (name "Net-(EPD_C2-Pad1)") (class "Default")
      (node (ref "EPD_C2") (pin "1") (pinfunction "1_1") (pintype "passive"))
      (node (ref "J1") (pin "5") (pinfunction "5_5") (pintype "bidirectional"))
    )
    (net (code "27") (name "Net-(EPD_C6-Pad1)") (class "Default")
      (node (ref "EPD_C6") (pin "1") (pinfunction "1_1") (pintype "passive"))
      (node (ref "J1") (pin "18") (pinfunction "18_18") (pintype "bidirectional"))
    )
    (net (code "28") (name "Net-(EPD_C7-Pad1)") (class "Default")
      (node (ref "EPD_C7") (pin "1") (pinfunction "1_1") (pintype "passive"))
      (node (ref "J1") (pin "19") (pinfunction "19_19") (pintype "bidirectional"))
    )
    (net (code "29") (name "Net-(EPD_C8-Pad1)") (class "Default")
      (node (ref "EPD_C8") (pin "1") (pinfunction "1_1") (pintype "passive"))
      (node (ref "J1") (pin "20") (pinfunction "20_20") (pintype "bidirectional"))
    )
    (net (code "30") (name "Net-(EPD_C10-Pad1)") (class "Default")
      (node (ref "EPD_C10") (pin "1") (pinfunction "1_1") (pintype "passive"))
      (node (ref "J1") (pin "22") (pinfunction "22_22") (pintype "bidirectional"))
    )
    (net (code "31") (name "Net-(EPD_C12-Pad1)") (class "Default")
      (node (ref "EPD_C12") (pin "1") (pinfunction "1_1") (pintype "passive"))
      (node (ref "J1") (pin "24") (pinfunction "24_24") (pintype "bidirectional"))
    )
    (net (code "32") (name "Net-(IC1-CT)") (class "Default")
      (node (ref "C_DELAY") (pin "1") (pinfunction "1_1") (pintype "passive"))
      (node (ref "IC1") (pin "5") (pinfunction "CT_5") (pintype "bidirectional"))
    )
    (net (code "33") (name "Net-(J2-PadA5)") (class "Default")
      (node (ref "J2") (pin "A5") (pinfunction "A5_A5") (pintype "bidirectional"))
      (node (ref "R2-USB1") (pin "2") (pinfunction "2_2") (pintype "passive"))
    )
    (net (code "34") (name "Net-(J2-PadB5)") (class "Default")
      (node (ref "J2") (pin "B5") (pinfunction "B5_B5") (pintype "bidirectional"))
      (node (ref "R2-USB") (pin "1") (pinfunction "1_1") (pintype "passive"))
    )
    (net (code "35") (name "Net-(MCP73831-PROG)") (class "Default")
      (node (ref "MCP73831") (pin "5") (pinfunction "PROG_5") (pintype "input"))
      (node (ref "R2_BAT") (pin "2") (pinfunction "2_2") (pintype "passive"))
    )
    (net (code "36") (name "Net-(MCP73831-STAT)") (class "Default")
      (node (ref "MCP73831") (pin "1") (pinfunction "STAT_1") (pintype "output"))
      (node (ref "R1_BAT") (pin "1") (pinfunction "1_1") (pintype "passive"))
    )
    (net (code "37") (name "PREVGH") (class "Default")
      (node (ref "D5") (pin "1") (pinfunction "K_1") (pintype "bidirectional"))
      (node (ref "EPD_C9") (pin "1") (pinfunction "1_1") (pintype "passive"))
      (node (ref "J1") (pin "21") (pinfunction "21_21") (pintype "bidirectional"))
    )
    (net (code "38") (name "PREVGL") (class "Default")
      (node (ref "D4") (pin "2") (pinfunction "A_2") (pintype "bidirectional"))
      (node (ref "EPD_C11") (pin "1") (pinfunction "1_1") (pintype "passive"))
      (node (ref "J1") (pin "23") (pinfunction "23_23") (pintype "bidirectional"))
    )
    (net (code "39") (name "RESE") (class "Default")
      (node (ref "J1") (pin "3") (pinfunction "3_3") (pintype "bidirectional"))
      (node (ref "Q3") (pin "2") (pinfunction "S_2") (pintype "bidirectional"))
      (node (ref "R3") (pin "1") (pinfunction "1_1") (pintype "passive"))
    )
    (net (code "40") (name "RESE'") (class "Default")
      (node (ref "R2") (pin "2") (pinfunction "2_2") (pintype "passive"))
      (node (ref "R3") (pin "2") (pinfunction "2_2") (pintype "passive"))
      (node (ref "SJ1") (pin "2") (pinfunction "2_2") (pintype "passive"))
    )
    (net (code "41") (name "RESET") (class "Default")
      (node (ref "C5") (pin "1") (pinfunction "1_1") (pintype "passive"))
      (node (ref "IC1") (pin "1") (pinfunction "VOUT_1") (pintype "bidirectional"))
      (node (ref "RESET_BUTTON") (pin "3") (pinfunction "3_3") (pintype "passive"))
      (node (ref "RESET_BUTTON") (pin "4") (pinfunction "4_4") (pintype "passive"))
      (node (ref "R_RESET") (pin "2") (pinfunction "2_2") (pintype "passive"))
      (node (ref "U2") (pin "3") (pinfunction "EN_3") (pintype "input"))
    )
    (net (code "42") (name "RTC_RST") (class "Default")
      (node (ref "U2") (pin "16") (pinfunction "IO18_16") (pintype "bidirectional"))
      (node (ref "U3") (pin "4") (pinfunction "~{RST}_4") (pintype "input"))
    )
    (net (code "43") (name "RX") (class "Default")
      (node (ref "TP2") (pin "TP") (pinfunction "TP_TP") (pintype "input"))
      (node (ref "U2") (pin "24") (pinfunction "RXD0/GPIO17_24") (pintype "bidirectional"))
    )
    (net (code "44") (name "SCK") (class "Default")
      (node (ref "D10") (pin "2") (pinfunction "2_2") (pintype "passive"))
      (node (ref "J1") (pin "13") (pinfunction "13_13") (pintype "bidirectional"))
      (node (ref "J4") (pin "P5") (pinfunction "CLK_P5") (pintype "bidirectional"))
      (node (ref "R6") (pin "1") (pinfunction "1_1") (pintype "passive"))
      (node (ref "TP8") (pin "TP") (pinfunction "TP_TP") (pintype "input"))
      (node (ref "U1") (pin "6") (pinfunction "CLK_6") (pintype "input"))
      (node (ref "U2") (pin "6") (pinfunction "IO6_6") (pintype "bidirectional"))
    )
    (net (code "45") (name "SCL") (class "Default")
      (node (ref "J3") (pin "4") (pinfunction "4_4") (pintype "passive"))
      (node (ref "R2-PINH") (pin "1") (pinfunction "1_1") (pintype "passive"))
      (node (ref "SENSOR2") (pin "4") (pinfunction "SCK_4") (pintype "input"))
      (node (ref "U2") (pin "20") (pinfunction "IO22_20") (pintype "bidirectional"))
      (node (ref "U3") (pin "16") (pinfunction "SCL_16") (pintype "input"))
      (node (ref "U4") (pin "7") (pinfunction "SCL_7") (pintype "input"))
    )
    (net (code "46") (name "SDA") (class "Default")
      (node (ref "J3") (pin "3") (pinfunction "3_3") (pintype "passive"))
      (node (ref "R1-PINH") (pin "1") (pinfunction "1_1") (pintype "passive"))
      (node (ref "SENSOR2") (pin "3") (pinfunction "SDI_3") (pintype "bidirectional"))
      (node (ref "U2") (pin "19") (pinfunction "IO21_19") (pintype "bidirectional"))
      (node (ref "U3") (pin "15") (pinfunction "SDA_15") (pintype "bidirectional"))
      (node (ref "U4") (pin "8") (pinfunction "SDA_8") (pintype "bidirectional"))
    )
    (net (code "47") (name "SRC") (class "Default")
      (node (ref "C4") (pin "2") (pinfunction "2_2") (pintype "passive"))
      (node (ref "D5") (pin "2") (pinfunction "A_2") (pintype "bidirectional"))
      (node (ref "L1") (pin "1") (pinfunction "1_1") (pintype "passive"))
      (node (ref "Q3") (pin "3") (pinfunction "D_3") (pintype "bidirectional"))
    )
    (net (code "48") (name "SS_SD") (class "Default")
      (node (ref "D8") (pin "2") (pinfunction "2_2") (pintype "passive"))
      (node (ref "J4") (pin "P2") (pinfunction "CD/DAT3_P2") (pintype "bidirectional"))
      (node (ref "R10") (pin "1") (pinfunction "1_1") (pintype "passive"))
      (node (ref "U2") (pin "4") (pinfunction "IO4_4") (pintype "bidirectional"))
    )
    (net (code "49") (name "TX") (class "Default")
      (node (ref "TP1") (pin "TP") (pinfunction "TP_TP") (pintype "input"))
      (node (ref "U2") (pin "25") (pinfunction "TXD0/GPIO16_25") (pintype "bidirectional"))
    )
    (net (code "50") (name "USB_D+") (class "Default")
      (node (ref "D1") (pin "1") (pinfunction "I/O1_1_1") (pintype "bidirectional"))
      (node (ref "U2") (pin "14") (pinfunction "IO13_14") (pintype "bidirectional"))
    )
    (net (code "51") (name "USB_D-") (class "Default")
      (node (ref "D1") (pin "3") (pinfunction "I/O2_1_3") (pintype "bidirectional"))
      (node (ref "U2") (pin "13") (pinfunction "IO12_13") (pintype "bidirectional"))
    )
    (net (code "52") (name "VBAT") (class "Default")
      (node (ref "C2_BAT") (pin "1") (pinfunction "1_1") (pintype "passive"))
      (node (ref "MCP73831") (pin "3") (pinfunction "VBAT_3") (pintype "power_in"))
      (node (ref "Q1") (pin "3") (pinfunction "D_3") (pintype "bidirectional"))
      (node (ref "TP3") (pin "TP") (pinfunction "TP_TP") (pintype "input"))
      (node (ref "U4") (pin "2") (pinfunction "CELL_2") (pintype "power_in"))
      (node (ref "U4") (pin "3") (pinfunction "VDD_3") (pintype "power_in"))
    )
    (net (code "53") (name "VBUS") (class "Default")
      (node (ref "C1_BAT") (pin "1") (pinfunction "1_1") (pintype "passive"))
      (node (ref "C4_USB") (pin "1") (pinfunction "1_1") (pintype "passive"))
      (node (ref "C5_USB") (pin "1") (pinfunction "1_1") (pintype "passive"))
      (node (ref "CHG_LED") (pin "A") (pinfunction "A_A") (pintype "passive"))
      (node (ref "D1") (pin "5") (pinfunction "VBUS_5") (pintype "bidirectional"))
      (node (ref "D2") (pin "2") (pinfunction "ANODE_2") (pintype "bidirectional"))
      (node (ref "MCP73831") (pin "4") (pinfunction "VIN_4") (pintype "power_in"))
      (node (ref "PFMF.050.1") (pin "2") (pinfunction "2_2") (pintype "passive"))
      (node (ref "Q1") (pin "1") (pinfunction "G_1") (pintype "bidirectional"))
      (node (ref "R1_PWRUSB") (pin "2") (pinfunction "2_2") (pintype "passive"))
      (node (ref "TP14") (pin "TP") (pinfunction "TP_TP") (pintype "input"))
    )
    (net (code "54") (name "VRTC") (class "Default")
      (node (ref "C10_SUPERCAP") (pin "2") (pinfunction "2_2") (pintype "passive"))
      (node (ref "C8") (pin "1") (pinfunction "1_1") (pintype "passive"))
      (node (ref "R_CAPACITOR") (pin "1") (pinfunction "1_1") (pintype "passive"))
      (node (ref "U3") (pin "14") (pinfunction "VBAT_14") (pintype "power_in"))
    )
    (net (code "55") (name "VUSB") (class "Default")
      (node (ref "J2") (pin "A4") (pinfunction "A4_A4") (pintype "bidirectional"))
      (node (ref "J2") (pin "A9") (pinfunction "A9_A9") (pintype "bidirectional"))
      (node (ref "J2") (pin "B4") (pinfunction "B4_B4") (pintype "bidirectional"))
      (node (ref "J2") (pin "B9") (pinfunction "B9_B9") (pintype "bidirectional"))
      (node (ref "PFMF.050.1") (pin "1") (pinfunction "1_1") (pintype "passive"))
    )
    (net (code "56") (name "unconnected-(IC1-NC-Pad4)") (class "Default")
      (node (ref "IC1") (pin "4") (pinfunction "NC_4") (pintype "no_connect"))
    )
    (net (code "57") (name "unconnected-(IC4-NC-Pad4)") (class "Default")
      (node (ref "IC4") (pin "4") (pinfunction "NC_4") (pintype "no_connect"))
    )
    (net (code "58") (name "unconnected-(J1-Pad1)") (class "Default")
      (node (ref "J1") (pin "1") (pinfunction "1_1") (pintype "bidirectional"))
    )
    (net (code "59") (name "unconnected-(J1-Pad6)") (class "Default")
      (node (ref "J1") (pin "6") (pinfunction "6_6") (pintype "bidirectional"))
    )
    (net (code "60") (name "unconnected-(J1-Pad7)") (class "Default")
      (node (ref "J1") (pin "7") (pinfunction "7_7") (pintype "bidirectional"))
    )
    (net (code "61") (name "unconnected-(J2-PadA8)") (class "Default")
      (node (ref "J2") (pin "A8") (pinfunction "A8_A8") (pintype "bidirectional"))
    )
    (net (code "62") (name "unconnected-(J2-PadB8)") (class "Default")
      (node (ref "J2") (pin "B8") (pinfunction "B8_B8") (pintype "bidirectional"))
    )
    (net (code "63") (name "unconnected-(J4-DAT1-PadP8)") (class "Default")
      (node (ref "J4") (pin "P8") (pinfunction "DAT1_P8") (pintype "bidirectional"))
    )
    (net (code "64") (name "unconnected-(J4-DAT2-PadP1)") (class "Default")
      (node (ref "J4") (pin "P1") (pinfunction "DAT2_P1") (pintype "bidirectional"))
    )
    (net (code "65") (name "unconnected-(J4-DETECTION_1-PadS1)") (class "Default")
      (node (ref "J4") (pin "S1") (pinfunction "DETECTION_1_S1") (pintype "bidirectional"))
    )
    (net (code "66") (name "unconnected-(J4-DETECTION_2-PadS2)") (class "Default")
      (node (ref "J4") (pin "S2") (pinfunction "DETECTION_2_S2") (pintype "bidirectional"))
    )
    (net (code "67") (name "unconnected-(U2-NC-Pad22)") (class "Default")
      (node (ref "U2") (pin "22") (pinfunction "NC_22") (pintype "no_connect"))
    )
    (net (code "68") (name "unconnected-(U4-~{ALERT}-Pad5)") (class "Default")
      (node (ref "U4") (pin "5") (pinfunction "~{ALERT}_5") (pintype "output"))
    )
  )
)
